# SCH_Modules.net
KiCad netlist of a schematic drawn in Altium Designer
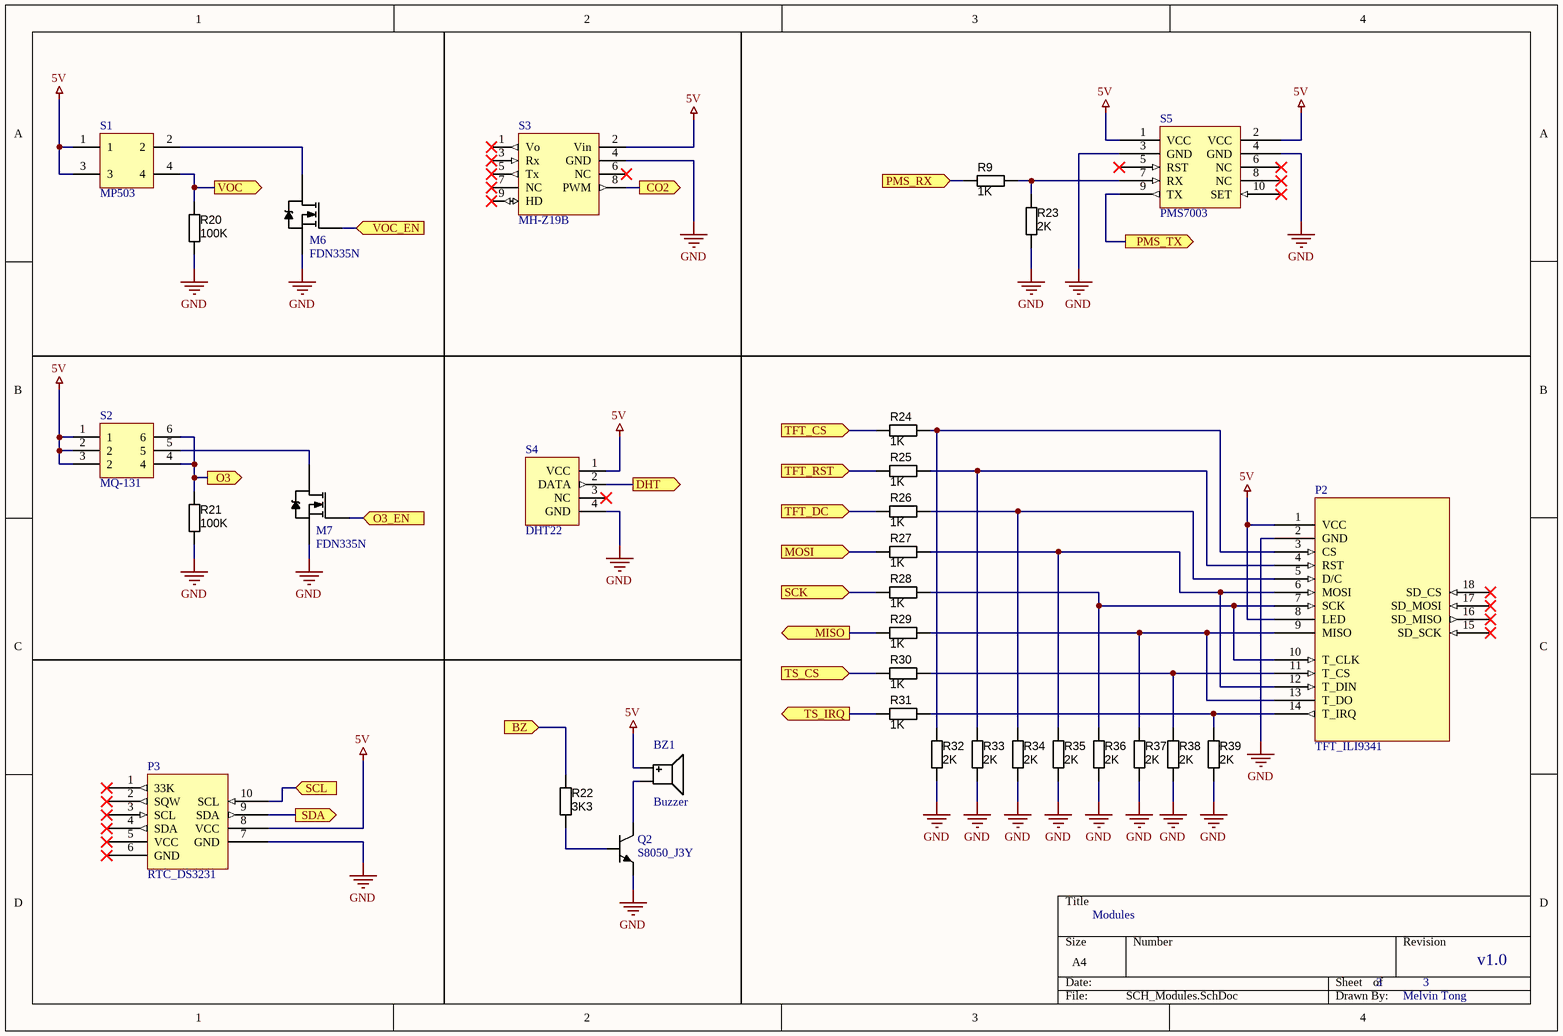
[diagram p0: SCH_Modules.SchDoc]

(export (version "E")
  (design (tool "Eeschema 10.0.6"))
  (components
    (comp (ref "BZ1")
      (value "Buzzer")
      (footprint "BZ_12085")
      (description "Buzzer passive 5 VAC")
      (libsource (lib "SchLib_AirMeter") (part "Buzzer"))
    )
    (comp (ref "M6")
      (value "FDN335N")
      (footprint "SOT23_213")
      (libsource (lib "SchLib_AirMeter") (part "NMOS"))
    )
    (comp (ref "M7")
      (value "FDN335N")
      (footprint "SOT23_213")
      (libsource (lib "SchLib_AirMeter") (part "NMOS"))
    )
    (comp (ref "P2")
      (value "TFT_ILI9341")
      (footprint "TFT_ILI9341")
      (libsource (lib "SchLib_AirMeter") (part "TFT_ILI9341"))
    )
    (comp (ref "P3")
      (value "RTC_DS3231")
      (footprint "DS3231 RTC")
      (description "Real Time Clock")
      (libsource (lib "SchLib_AirMeter") (part "RTC_DS3231"))
    )
    (comp (ref "Q2")
      (value "S8050_J3Y")
      (footprint "SOT23_213")
      (libsource (lib "SchLib_AirMeter") (part "NPN"))
    )
    (comp (ref "R9")
      (value "1K")
      (footprint "RESC3216X70N")
      (description "Resistor SMD, 1206")
      (libsource (lib "SchLib_AirMeter") (part "RES_1K"))
    )
    (comp (ref "R20")
      (value "100K")
      (footprint "RESC3216X70N")
      (description "Resistor SMD, 1206")
      (libsource (lib "SchLib_AirMeter") (part "RES_100K"))
    )
    (comp (ref "R21")
      (value "100K")
      (footprint "RESC3216X70N")
      (description "Resistor SMD, 1206")
      (libsource (lib "SchLib_AirMeter") (part "RES_100K"))
    )
    (comp (ref "R22")
      (value "3K3")
      (footprint "RESC3216X70N")
      (description "Resistor SMD, 1206")
      (libsource (lib "SchLib_AirMeter") (part "RES_3K3"))
    )
    (comp (ref "R23")
      (value "2K")
      (footprint "RESC3216X70N")
      (description "Resistor SMD, 1206")
      (libsource (lib "SchLib_AirMeter") (part "RES_2K"))
    )
    (comp (ref "R24")
      (value "1K")
      (footprint "RESC3216X70N")
      (description "Resistor SMD, 1206")
      (libsource (lib "SchLib_AirMeter") (part "RES_1K"))
    )
    (comp (ref "R25")
      (value "1K")
      (footprint "RESC3216X70N")
      (description "Resistor SMD, 1206")
      (libsource (lib "SchLib_AirMeter") (part "RES_1K"))
    )
    (comp (ref "R26")
      (value "1K")
      (footprint "RESC3216X70N")
      (description "Resistor SMD, 1206")
      (libsource (lib "SchLib_AirMeter") (part "RES_1K"))
    )
    (comp (ref "R27")
      (value "1K")
      (footprint "RESC3216X70N")
      (description "Resistor SMD, 1206")
      (libsource (lib "SchLib_AirMeter") (part "RES_1K"))
    )
    (comp (ref "R28")
      (value "1K")
      (footprint "RESC3216X70N")
      (description "Resistor SMD, 1206")
      (libsource (lib "SchLib_AirMeter") (part "RES_1K"))
    )
    (comp (ref "R29")
      (value "1K")
      (footprint "RESC3216X70N")
      (description "Resistor SMD, 1206")
      (libsource (lib "SchLib_AirMeter") (part "RES_1K"))
    )
    (comp (ref "R30")
      (value "1K")
      (footprint "RESC3216X70N")
      (description "Resistor SMD, 1206")
      (libsource (lib "SchLib_AirMeter") (part "RES_1K"))
    )
    (comp (ref "R31")
      (value "1K")
      (footprint "RESC3216X70N")
      (description "Resistor SMD, 1206")
      (libsource (lib "SchLib_AirMeter") (part "RES_1K"))
    )
    (comp (ref "R32")
      (value "2K")
      (footprint "RESC3216X70N")
      (description "Resistor SMD, 1206")
      (libsource (lib "SchLib_AirMeter") (part "RES_2K"))
    )
    (comp (ref "R33")
      (value "2K")
      (footprint "RESC3216X70N")
      (description "Resistor SMD, 1206")
      (libsource (lib "SchLib_AirMeter") (part "RES_2K"))
    )
    (comp (ref "R34")
      (value "2K")
      (footprint "RESC3216X70N")
      (description "Resistor SMD, 1206")
      (libsource (lib "SchLib_AirMeter") (part "RES_2K"))
    )
    (comp (ref "R35")
      (value "2K")
      (footprint "RESC3216X70N")
      (description "Resistor SMD, 1206")
      (libsource (lib "SchLib_AirMeter") (part "RES_2K"))
    )
    (comp (ref "R36")
      (value "2K")
      (footprint "RESC3216X70N")
      (description "Resistor SMD, 1206")
      (libsource (lib "SchLib_AirMeter") (part "RES_2K"))
    )
    (comp (ref "R37")
      (value "2K")
      (footprint "RESC3216X70N")
      (description "Resistor SMD, 1206")
      (libsource (lib "SchLib_AirMeter") (part "RES_2K"))
    )
    (comp (ref "R38")
      (value "2K")
      (footprint "RESC3216X70N")
      (description "Resistor SMD, 1206")
      (libsource (lib "SchLib_AirMeter") (part "RES_2K"))
    )
    (comp (ref "R39")
      (value "2K")
      (footprint "RESC3216X70N")
      (description "Resistor SMD, 1206")
      (libsource (lib "SchLib_AirMeter") (part "RES_2K"))
    )
    (comp (ref "S1")
      (value "MP503")
      (footprint "MP503 VOC Sensor")
      (description "VOC Sensor")
      (libsource (lib "SchLib_AirMeter") (part "MP503"))
    )
    (comp (ref "S2")
      (value "MQ-131")
      (footprint "MQ-131 Ozone Sensor")
      (description "Ozone Sensor")
      (libsource (lib "SchLib_AirMeter") (part "MQ-131"))
    )
    (comp (ref "S3")
      (value "MH-Z19B")
      (footprint "MH-Z19B CO2 Sensor")
      (description "CO2 Sensor")
      (libsource (lib "SchLib_AirMeter") (part "MH-Z19B"))
    )
    (comp (ref "S4") (value "DHT22") (footprint "DHT22") (libsource (lib "SchLib_AirMeter") (part "DHT22")))
    (comp (ref "S5")
      (value "PMS7003")
      (footprint "PMS7003")
      (description "Particle air sensor. 1um, 2.5um, 10um")
      (libsource (lib "SchLib_AirMeter") (part "PMS7003"))
    )
  )
  (nets
    (net (code "1") (name "/BZ") (class "Default")
      (node (ref "R22") (pin "1") (pinfunction "1_1") (pintype "passive"))
    )
    (net (code "2") (name "/CO2") (class "Default")
      (node (ref "S3") (pin "8") (pinfunction "PWM_8") (pintype "output"))
    )
    (net (code "3") (name "/DHT") (class "Default")
      (node (ref "S4") (pin "2") (pinfunction "DATA_2") (pintype "output"))
    )
    (net (code "4") (name "/MISO") (class "Default")
      (node (ref "R29") (pin "1") (pinfunction "1_1") (pintype "passive"))
    )
    (net (code "5") (name "/MOSI") (class "Default")
      (node (ref "R27") (pin "1") (pinfunction "1_1") (pintype "passive"))
    )
    (net (code "6") (name "/O3") (class "Default")
      (node (ref "R21") (pin "1") (pinfunction "1_1") (pintype "passive"))
      (node (ref "S2") (pin "4") (pinfunction "4_4") (pintype "passive"))
      (node (ref "S2") (pin "6") (pinfunction "6_6") (pintype "passive"))
    )
    (net (code "7") (name "/O3_EN") (class "Default")
      (node (ref "M7") (pin "1") (pinfunction "G_1") (pintype "passive"))
    )
    (net (code "8") (name "/PMS_RX") (class "Default")
      (node (ref "R9") (pin "1") (pinfunction "1_1") (pintype "passive"))
    )
    (net (code "9") (name "/PMS_TX") (class "Default")
      (node (ref "S5") (pin "9") (pinfunction "TX_9") (pintype "output"))
    )
    (net (code "10") (name "/SCK") (class "Default")
      (node (ref "R28") (pin "1") (pinfunction "1_1") (pintype "passive"))
    )
    (net (code "11") (name "/SCL") (class "Default")
      (node (ref "P3") (pin "10") (pinfunction "SCL_10") (pintype "input"))
    )
    (net (code "12") (name "/SDA") (class "Default")
      (node (ref "P3") (pin "9") (pinfunction "SDA_9") (pintype "output"))
    )
    (net (code "13") (name "/TFT_CS") (class "Default")
      (node (ref "R24") (pin "1") (pinfunction "1_1") (pintype "passive"))
    )
    (net (code "14") (name "/TFT_DC") (class "Default")
      (node (ref "R26") (pin "1") (pinfunction "1_1") (pintype "passive"))
    )
    (net (code "15") (name "/TFT_RST") (class "Default")
      (node (ref "R25") (pin "1") (pinfunction "1_1") (pintype "passive"))
    )
    (net (code "16") (name "/TS_CS") (class "Default")
      (node (ref "R30") (pin "1") (pinfunction "1_1") (pintype "passive"))
    )
    (net (code "17") (name "/TS_IRQ") (class "Default")
      (node (ref "R31") (pin "1") (pinfunction "1_1") (pintype "passive"))
    )
    (net (code "18") (name "/VOC") (class "Default")
      (node (ref "R20") (pin "1") (pinfunction "1_1") (pintype "passive"))
      (node (ref "S1") (pin "4") (pinfunction "4_4") (pintype "passive"))
    )
    (net (code "19") (name "/VOC_EN") (class "Default")
      (node (ref "M6") (pin "1") (pinfunction "G_1") (pintype "passive"))
    )
    (net (code "20") (name "5V") (class "Default")
      (node (ref "BZ1") (pin "1") (pinfunction "Positive_1") (pintype "passive"))
      (node (ref "P2") (pin "1") (pinfunction "VCC_1") (pintype "power_in"))
      (node (ref "P2") (pin "8") (pinfunction "LED_8") (pintype "power_in"))
      (node (ref "P3") (pin "8") (pinfunction "VCC_8") (pintype "power_in"))
      (node (ref "S1") (pin "1") (pinfunction "1_1") (pintype "passive"))
      (node (ref "S1") (pin "3") (pinfunction "3_3") (pintype "passive"))
      (node (ref "S2") (pin "1") (pinfunction "1_1") (pintype "passive"))
      (node (ref "S2") (pin "2") (pinfunction "2_2") (pintype "passive"))
      (node (ref "S2") (pin "3") (pinfunction "2_3") (pintype "passive"))
      (node (ref "S3") (pin "2") (pinfunction "Vin_2") (pintype "power_in"))
      (node (ref "S4") (pin "1") (pinfunction "VCC_1") (pintype "power_in"))
      (node (ref "S5") (pin "1") (pinfunction "VCC_1") (pintype "power_in"))
      (node (ref "S5") (pin "2") (pinfunction "VCC_2") (pintype "power_in"))
    )
    (net (code "21") (name "GND") (class "Default")
      (node (ref "M6") (pin "2") (pinfunction "S_2") (pintype "passive"))
      (node (ref "M7") (pin "2") (pinfunction "S_2") (pintype "passive"))
      (node (ref "P2") (pin "2") (pinfunction "GND_2") (pintype "power_in"))
      (node (ref "P3") (pin "7") (pinfunction "GND_7") (pintype "power_in"))
      (node (ref "Q2") (pin "2") (pinfunction "E_2") (pintype "passive"))
      (node (ref "R20") (pin "2") (pinfunction "2_2") (pintype "passive"))
      (node (ref "R21") (pin "2") (pinfunction "2_2") (pintype "passive"))
      (node (ref "R23") (pin "2") (pinfunction "2_2") (pintype "passive"))
      (node (ref "R32") (pin "2") (pinfunction "2_2") (pintype "passive"))
      (node (ref "R33") (pin "2") (pinfunction "2_2") (pintype "passive"))
      (node (ref "R34") (pin "2") (pinfunction "2_2") (pintype "passive"))
      (node (ref "R35") (pin "2") (pinfunction "2_2") (pintype "passive"))
      (node (ref "R36") (pin "2") (pinfunction "2_2") (pintype "passive"))
      (node (ref "R37") (pin "2") (pinfunction "2_2") (pintype "passive"))
      (node (ref "R38") (pin "2") (pinfunction "2_2") (pintype "passive"))
      (node (ref "R39") (pin "2") (pinfunction "2_2") (pintype "passive"))
      (node (ref "S3") (pin "4") (pinfunction "GND_4") (pintype "power_in"))
      (node (ref "S4") (pin "4") (pinfunction "GND_4") (pintype "power_in"))
      (node (ref "S5") (pin "3") (pinfunction "GND_3") (pintype "power_in"))
      (node (ref "S5") (pin "4") (pinfunction "GND_4") (pintype "power_in"))
    )
    (net (code "22") (name "Net-(BZ1-Negative)") (class "Default")
      (node (ref "BZ1") (pin "2") (pinfunction "Negative_2") (pintype "passive"))
      (node (ref "Q2") (pin "3") (pinfunction "C_3") (pintype "passive"))
    )
    (net (code "23") (name "Net-(M6-D)") (class "Default")
      (node (ref "M6") (pin "3") (pinfunction "D_3") (pintype "passive"))
      (node (ref "S1") (pin "2") (pinfunction "2_2") (pintype "passive"))
    )
    (net (code "24") (name "Net-(M7-D)") (class "Default")
      (node (ref "M7") (pin "3") (pinfunction "D_3") (pintype "passive"))
      (node (ref "S2") (pin "5") (pinfunction "5_5") (pintype "passive"))
    )
    (net (code "25") (name "Net-(P2-CS)") (class "Default")
      (node (ref "P2") (pin "3") (pinfunction "CS_3") (pintype "input"))
      (node (ref "R24") (pin "2") (pinfunction "2_2") (pintype "passive"))
      (node (ref "R32") (pin "1") (pinfunction "1_1") (pintype "passive"))
    )
    (net (code "26") (name "Net-(P2-D{slash}C)") (class "Default")
      (node (ref "P2") (pin "5") (pinfunction "D/C_5") (pintype "input"))
      (node (ref "R26") (pin "2") (pinfunction "2_2") (pintype "passive"))
      (node (ref "R34") (pin "1") (pinfunction "1_1") (pintype "passive"))
    )
    (net (code "27") (name "Net-(P2-MISO)") (class "Default")
      (node (ref "P2") (pin "13") (pinfunction "T_DO_13") (pintype "passive"))
      (node (ref "P2") (pin "9") (pinfunction "MISO_9") (pintype "passive"))
      (node (ref "R29") (pin "2") (pinfunction "2_2") (pintype "passive"))
      (node (ref "R37") (pin "1") (pinfunction "1_1") (pintype "passive"))
    )
    (net (code "28") (name "Net-(P2-MOSI)") (class "Default")
      (node (ref "P2") (pin "12") (pinfunction "T_DIN_12") (pintype "input"))
      (node (ref "P2") (pin "6") (pinfunction "MOSI_6") (pintype "input"))
      (node (ref "R27") (pin "2") (pinfunction "2_2") (pintype "passive"))
      (node (ref "R35") (pin "1") (pinfunction "1_1") (pintype "passive"))
    )
    (net (code "29") (name "Net-(P2-RST)") (class "Default")
      (node (ref "P2") (pin "4") (pinfunction "RST_4") (pintype "input"))
      (node (ref "R25") (pin "2") (pinfunction "2_2") (pintype "passive"))
      (node (ref "R33") (pin "1") (pinfunction "1_1") (pintype "passive"))
    )
    (net (code "30") (name "Net-(P2-SCK)") (class "Default")
      (node (ref "P2") (pin "10") (pinfunction "T_CLK_10") (pintype "input"))
      (node (ref "P2") (pin "7") (pinfunction "SCK_7") (pintype "input"))
      (node (ref "R28") (pin "2") (pinfunction "2_2") (pintype "passive"))
      (node (ref "R36") (pin "1") (pinfunction "1_1") (pintype "passive"))
    )
    (net (code "31") (name "Net-(P2-T_CS)") (class "Default")
      (node (ref "P2") (pin "11") (pinfunction "T_CS_11") (pintype "input"))
      (node (ref "R30") (pin "2") (pinfunction "2_2") (pintype "passive"))
      (node (ref "R38") (pin "1") (pinfunction "1_1") (pintype "passive"))
    )
    (net (code "32") (name "Net-(P2-T_IRQ)") (class "Default")
      (node (ref "P2") (pin "14") (pinfunction "T_IRQ_14") (pintype "output"))
      (node (ref "R31") (pin "2") (pinfunction "2_2") (pintype "passive"))
      (node (ref "R39") (pin "1") (pinfunction "1_1") (pintype "passive"))
    )
    (net (code "33") (name "Net-(Q2-B)") (class "Default")
      (node (ref "Q2") (pin "1") (pinfunction "B_1") (pintype "passive"))
      (node (ref "R22") (pin "2") (pinfunction "2_2") (pintype "passive"))
    )
    (net (code "34") (name "Net-(S5-RX)") (class "Default")
      (node (ref "R23") (pin "1") (pinfunction "1_1") (pintype "passive"))
      (node (ref "R9") (pin "2") (pinfunction "2_2") (pintype "passive"))
      (node (ref "S5") (pin "7") (pinfunction "RX_7") (pintype "input"))
    )
    (net (code "35") (name "unconnected-(P2-SD_CS-Pad18)") (class "Default")
      (node (ref "P2") (pin "18") (pinfunction "SD_CS_18") (pintype "input+no_connect"))
    )
    (net (code "36") (name "unconnected-(P2-SD_MISO-Pad16)") (class "Default")
      (node (ref "P2") (pin "16") (pinfunction "SD_MISO_16") (pintype "output+no_connect"))
    )
    (net (code "37") (name "unconnected-(P2-SD_MOSI-Pad17)") (class "Default")
      (node (ref "P2") (pin "17") (pinfunction "SD_MOSI_17") (pintype "input+no_connect"))
    )
    (net (code "38") (name "unconnected-(P2-SD_SCK-Pad15)") (class "Default")
      (node (ref "P2") (pin "15") (pinfunction "SD_SCK_15") (pintype "input+no_connect"))
    )
    (net (code "39") (name "unconnected-(P3-33K-Pad1)") (class "Default")
      (node (ref "P3") (pin "1") (pinfunction "33K_1") (pintype "output+no_connect"))
    )
    (net (code "40") (name "unconnected-(P3-GND-Pad6)") (class "Default")
      (node (ref "P3") (pin "6") (pinfunction "GND_6") (pintype "power_in+no_connect"))
    )
    (net (code "41") (name "unconnected-(P3-SCL-Pad3)") (class "Default")
      (node (ref "P3") (pin "3") (pinfunction "SCL_3") (pintype "input+no_connect"))
    )
    (net (code "42") (name "unconnected-(P3-SDA-Pad4)") (class "Default")
      (node (ref "P3") (pin "4") (pinfunction "SDA_4") (pintype "output+no_connect"))
    )
    (net (code "43") (name "unconnected-(P3-SQW-Pad2)") (class "Default")
      (node (ref "P3") (pin "2") (pinfunction "SQW_2") (pintype "output+no_connect"))
    )
    (net (code "44") (name "unconnected-(P3-VCC-Pad5)") (class "Default")
      (node (ref "P3") (pin "5") (pinfunction "VCC_5") (pintype "power_in+no_connect"))
    )
    (net (code "45") (name "unconnected-(S3-HD-Pad9)") (class "Default")
      (node (ref "S3") (pin "9") (pinfunction "HD_9") (pintype "bidirectional+no_connect"))
    )
    (net (code "46") (name "unconnected-(S3-NC-Pad6)") (class "Default")
      (node (ref "S3") (pin "6") (pinfunction "NC_6") (pintype "passive+no_connect"))
    )
    (net (code "47") (name "unconnected-(S3-NC-Pad7)") (class "Default")
      (node (ref "S3") (pin "7") (pinfunction "NC_7") (pintype "passive+no_connect"))
    )
    (net (code "48") (name "unconnected-(S3-Rx-Pad3)") (class "Default")
      (node (ref "S3") (pin "3") (pinfunction "Rx_3") (pintype "input+no_connect"))
    )
    (net (code "49") (name "unconnected-(S3-Tx-Pad5)") (class "Default")
      (node (ref "S3") (pin "5") (pinfunction "Tx_5") (pintype "output+no_connect"))
    )
    (net (code "50") (name "unconnected-(S3-Vo-Pad1)") (class "Default")
      (node (ref "S3") (pin "1") (pinfunction "Vo_1") (pintype "output+no_connect"))
    )
    (net (code "51") (name "unconnected-(S4-NC-Pad3)") (class "Default")
      (node (ref "S4") (pin "3") (pinfunction "NC_3") (pintype "power_in+no_connect"))
    )
    (net (code "52") (name "unconnected-(S5-NC-Pad6)") (class "Default")
      (node (ref "S5") (pin "6") (pinfunction "NC_6") (pintype "passive+no_connect"))
    )
    (net (code "53") (name "unconnected-(S5-NC-Pad8)") (class "Default")
      (node (ref "S5") (pin "8") (pinfunction "NC_8") (pintype "passive+no_connect"))
    )
    (net (code "54") (name "unconnected-(S5-RST-Pad5)") (class "Default")
      (node (ref "S5") (pin "5") (pinfunction "RST_5") (pintype "input+no_connect"))
    )
    (net (code "55") (name "unconnected-(S5-SET-Pad10)") (class "Default")
      (node (ref "S5") (pin "10") (pinfunction "SET_10") (pintype "input+no_connect"))
    )
  )
)
